# MCU.net
KiCad netlist of a schematic drawn in Altium Designer
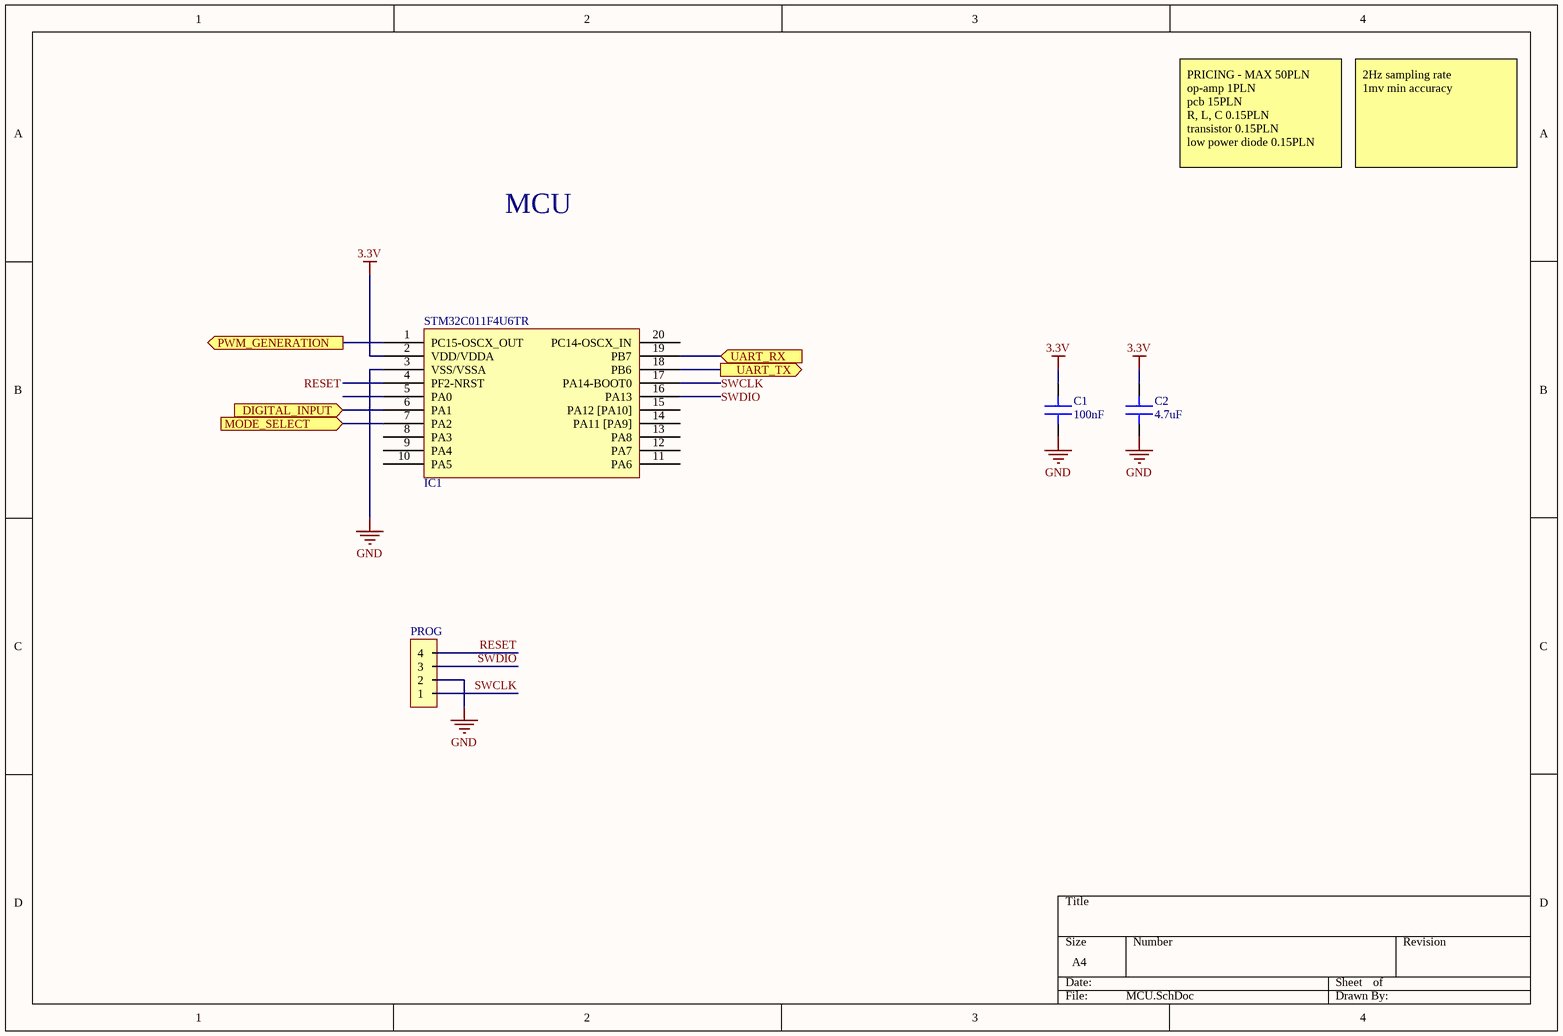
[diagram p0: MCU.SchDoc]

(export (version "E")
  (design (tool "Eeschema 10.0.6"))
  (components
    (comp (ref "C1")
      (value "100nF")
      (footprint "C 0603")
      (description "MLCC Capacitor")
      (libsource (lib "sigma-delta-adc-uart") (part "Capacitor"))
    )
    (comp (ref "C2")
      (value "4.7uF")
      (footprint "C 0603")
      (description "MLCC Capacitor")
      (libsource (lib "sigma-delta-adc-uart") (part "Capacitor"))
    )
    (comp (ref "IC1")
      (value "STM32C011F4U6TR")
      (footprint "UFQFPN20 - byMe")
      (libsource (lib "sigma-delta-adc-uart") (part "STM32C011F4U6TR"))
    )
    (comp (ref "PROG")
      (value "4 PIN")
      (footprint "BM04B-SRSS-TB")
      (libsource (lib "sigma-delta-adc-uart") (part "4 PIN"))
    )
  )
  (nets
    (net (code "1") (name "/DIGITAL_INPUT") (class "Default")
      (node (ref "IC1") (pin "6") (pinfunction "PA1_6") (pintype "passive"))
    )
    (net (code "2") (name "/MODE_SELECT") (class "Default")
      (node (ref "IC1") (pin "7") (pinfunction "PA2_7") (pintype "passive"))
    )
    (net (code "3") (name "/PWM_GENERATION") (class "Default")
      (node (ref "IC1") (pin "1") (pinfunction "PC15-OSCX_OUT_1") (pintype "passive"))
    )
    (net (code "4") (name "/RESET") (class "Default")
      (node (ref "IC1") (pin "4") (pinfunction "PF2-NRST_4") (pintype "passive"))
      (node (ref "PROG") (pin "4") (pinfunction "4_4") (pintype "passive"))
    )
    (net (code "5") (name "/SWCLK") (class "Default")
      (node (ref "IC1") (pin "17") (pinfunction "PA14-BOOT0_17") (pintype "passive"))
      (node (ref "PROG") (pin "1") (pinfunction "1_1") (pintype "passive"))
    )
    (net (code "6") (name "/SWDIO") (class "Default")
      (node (ref "IC1") (pin "16") (pinfunction "PA13_16") (pintype "passive"))
      (node (ref "PROG") (pin "3") (pinfunction "3_3") (pintype "passive"))
    )
    (net (code "7") (name "/UART_RX") (class "Default")
      (node (ref "IC1") (pin "19") (pinfunction "PB7_19") (pintype "passive"))
    )
    (net (code "8") (name "/UART_TX") (class "Default")
      (node (ref "IC1") (pin "18") (pinfunction "PB6_18") (pintype "passive"))
    )
    (net (code "9") (name "3.3V") (class "Default")
      (node (ref "C1") (pin "1") (pinfunction "1_1") (pintype "passive"))
      (node (ref "C2") (pin "1") (pinfunction "1_1") (pintype "passive"))
      (node (ref "IC1") (pin "2") (pinfunction "VDD/VDDA_2") (pintype "passive"))
    )
    (net (code "10") (name "GND") (class "Default")
      (node (ref "C1") (pin "2") (pinfunction "2_2") (pintype "passive"))
      (node (ref "C2") (pin "2") (pinfunction "2_2") (pintype "passive"))
      (node (ref "IC1") (pin "3") (pinfunction "VSS/VSSA_3") (pintype "passive"))
      (node (ref "PROG") (pin "2") (pinfunction "2_2") (pintype "passive"))
    )
    (net (code "11") (name "unconnected-(IC1-PA0-Pad5)") (class "Default")
      (node (ref "IC1") (pin "5") (pinfunction "PA0_5") (pintype "passive"))
    )
    (net (code "12") (name "unconnected-(IC1-PA3-Pad8)") (class "Default")
      (node (ref "IC1") (pin "8") (pinfunction "PA3_8") (pintype "passive"))
    )
    (net (code "13") (name "unconnected-(IC1-PA4-Pad9)") (class "Default")
      (node (ref "IC1") (pin "9") (pinfunction "PA4_9") (pintype "passive"))
    )
    (net (code "14") (name "unconnected-(IC1-PA5-Pad10)") (class "Default")
      (node (ref "IC1") (pin "10") (pinfunction "PA5_10") (pintype "passive"))
    )
    (net (code "15") (name "unconnected-(IC1-PA6-Pad11)") (class "Default")
      (node (ref "IC1") (pin "11") (pinfunction "PA6_11") (pintype "passive"))
    )
    (net (code "16") (name "unconnected-(IC1-PA7-Pad12)") (class "Default")
      (node (ref "IC1") (pin "12") (pinfunction "PA7_12") (pintype "passive"))
    )
    (net (code "17") (name "unconnected-(IC1-PA8-Pad13)") (class "Default")
      (node (ref "IC1") (pin "13") (pinfunction "PA8_13") (pintype "passive"))
    )
    (net (code "18") (name "unconnected-(IC1-PA11_[PA9]-Pad14)") (class "Default")
      (node (ref "IC1") (pin "14") (pinfunction "PA11_[PA9]_14") (pintype "passive"))
    )
    (net (code "19") (name "unconnected-(IC1-PA12_[PA10]-Pad15)") (class "Default")
      (node (ref "IC1") (pin "15") (pinfunction "PA12_[PA10]_15") (pintype "passive"))
    )
    (net (code "20") (name "unconnected-(IC1-PC14-OSCX_IN-Pad20)") (class "Default")
      (node (ref "IC1") (pin "20") (pinfunction "PC14-OSCX_IN_20") (pintype "passive"))
    )
  )
)
